# frekvensHack_schematic.net
KiCad netlist of a schematic drawn in EAGLE
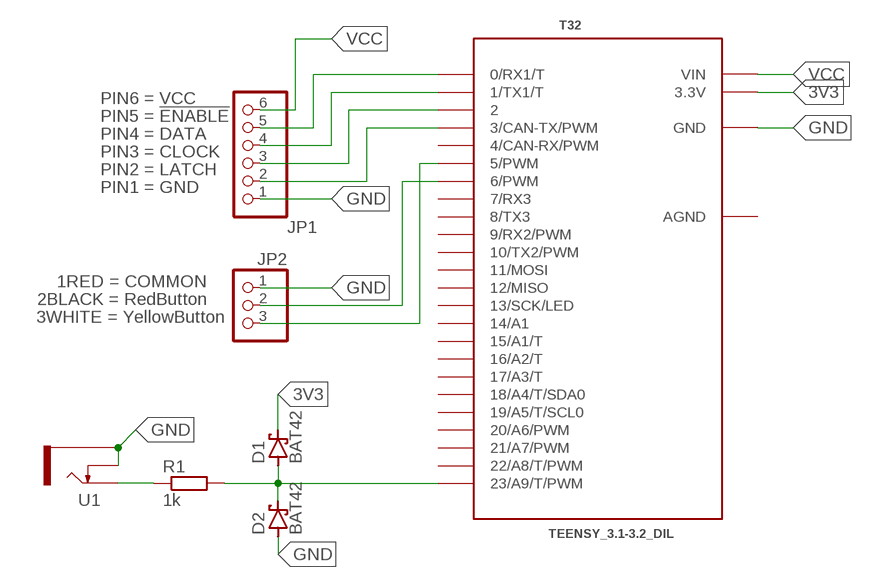
[diagram p0: schematic, sheet 1]

(export (version "E")
  (design (tool "Eeschema 10.0.6"))
  (components
    (comp (ref "D1")
      (value "BAT42")
      (footprint "eagle-import:DO35-10")
      (libsource (lib "eagle-import") (part "BAT42"))
    )
    (comp (ref "D2")
      (value "BAT42")
      (footprint "eagle-import:DO35-10")
      (libsource (lib "eagle-import") (part "BAT42"))
    )
    (comp (ref "JP1")
      (value "PINHD-1X6")
      (footprint "eagle-import:1X06")
      (fields
        (field (name "PIN1") "GND")
        (field (name "PIN2") "LATCH")
        (field (name "PIN3") "CLOCK")
        (field (name "PIN4") "DATA")
        (field (name "PIN5") "!ENABLE")
        (field (name "PIN6") "VCC")
      )
      (libsource (lib "eagle-import") (part "PINHD-1X6"))
    )
    (comp (ref "JP2")
      (value "PINHD-1X3")
      (footprint "eagle-import:1X03")
      (fields
        (field (name "1RED") "COMMON")
        (field (name "2BLACK") "RedButton")
        (field (name "3WHITE") "YellowButton")
      )
      (libsource (lib "eagle-import") (part "PINHD-1X3"))
    )
    (comp (ref "R1")
      (value "1k")
      (footprint "eagle-import:10MM_RESISTOR")
      (libsource (lib "eagle-import") (part "RESISTOR10MM_RESISTOR"))
    )
    (comp (ref "T32")
      (value "TEENSY_3.1-3.2_DIL")
      (footprint "eagle-import:TEENSY_3.0-3.2&LC_DIL")
      (libsource (lib "eagle-import") (part "TEENSY_3.1-3.2_DIL"))
    )
    (comp (ref "U1")
      (value "THONKICONNNEW")
      (footprint "eagle-import:WQP-PJ301M-12_JACK")
      (libsource (lib "eagle-import") (part "THONKICONNNEW"))
    )
  )
  (nets
    (net (code "1") (name "/AGND") (class "Default")
      (node (ref "T32") (pin "AGND") (pinfunction "AGND_AGND") (pintype "power_in"))
    )
    (net (code "2") (name "3V3") (class "Default")
      (node (ref "D1") (pin "C") (pinfunction "C_C") (pintype "passive"))
      (node (ref "T32") (pin "3.3V") (pinfunction "3.3V_3.3V") (pintype "power_in"))
    )
    (net (code "3") (name "GND") (class "Default")
      (node (ref "D2") (pin "A") (pinfunction "A_A") (pintype "passive"))
      (node (ref "JP1") (pin "1") (pinfunction "1_1") (pintype "passive"))
      (node (ref "JP2") (pin "1") (pinfunction "1_1") (pintype "passive"))
      (node (ref "T32") (pin "GND") (pinfunction "GND_GND") (pintype "power_in"))
      (node (ref "U1") (pin "P$2_SWITCH") (pinfunction "SWITCH_P$2_SWITCH") (pintype "passive"))
      (node (ref "U1") (pin "P$3_SLEEVE") (pinfunction "SLEEVE_P$3_SLEEVE") (pintype "passive"))
    )
    (net (code "4") (name "Net-(JP1-Pad3)") (class "Default")
      (node (ref "JP1") (pin "3") (pinfunction "3_3") (pintype "passive"))
      (node (ref "T32") (pin "2") (pinfunction "2_2") (pintype "bidirectional"))
    )
    (net (code "5") (name "Net-(T32-0{slash}RX1{slash}T)") (class "Default")
      (node (ref "JP1") (pin "5") (pinfunction "5_5") (pintype "passive"))
      (node (ref "T32") (pin "0") (pinfunction "0/RX1/T_0") (pintype "bidirectional"))
    )
    (net (code "6") (name "Net-(T32-1{slash}TX1{slash}T)") (class "Default")
      (node (ref "JP1") (pin "4") (pinfunction "4_4") (pintype "passive"))
      (node (ref "T32") (pin "1") (pinfunction "1/TX1/T_1") (pintype "bidirectional"))
    )
    (net (code "7") (name "Net-(T32-3{slash}CAN-TX{slash}PWM)") (class "Default")
      (node (ref "JP1") (pin "2") (pinfunction "2_2") (pintype "passive"))
      (node (ref "T32") (pin "3") (pinfunction "3/CAN-TX/PWM_3") (pintype "bidirectional"))
    )
    (net (code "8") (name "Net-(T32-5{slash}PWM)") (class "Default")
      (node (ref "JP2") (pin "3") (pinfunction "3_3") (pintype "passive"))
      (node (ref "T32") (pin "5") (pinfunction "5/PWM_5") (pintype "bidirectional"))
    )
    (net (code "9") (name "Net-(T32-6{slash}PWM)") (class "Default")
      (node (ref "JP2") (pin "2") (pinfunction "2_2") (pintype "passive"))
      (node (ref "T32") (pin "6") (pinfunction "6/PWM_6") (pintype "bidirectional"))
    )
    (net (code "10") (name "Net-(T32-23{slash}A9{slash}T{slash}PWM)") (class "Default")
      (node (ref "D1") (pin "A") (pinfunction "A_A") (pintype "passive"))
      (node (ref "D2") (pin "C") (pinfunction "C_C") (pintype "passive"))
      (node (ref "R1") (pin "2") (pinfunction "2_2") (pintype "passive"))
      (node (ref "T32") (pin "23/A9") (pinfunction "23/A9/T/PWM_23/A9") (pintype "bidirectional"))
    )
    (net (code "11") (name "Net-(U1-TIP)") (class "Default")
      (node (ref "R1") (pin "1") (pinfunction "1_1") (pintype "passive"))
      (node (ref "U1") (pin "P$1_TIP") (pinfunction "TIP_P$1_TIP") (pintype "passive"))
    )
    (net (code "12") (name "VCC") (class "Default")
      (node (ref "JP1") (pin "6") (pinfunction "6_6") (pintype "passive"))
      (node (ref "T32") (pin "VIN") (pinfunction "VIN_VIN") (pintype "power_in"))
    )
    (net (code "13") (name "unconnected-(T32-4{slash}CAN-RX{slash}PWM-Pad4)") (class "Default")
      (node (ref "T32") (pin "4") (pinfunction "4/CAN-RX/PWM_4") (pintype "bidirectional"))
    )
    (net (code "14") (name "unconnected-(T32-7{slash}RX3-Pad7)") (class "Default")
      (node (ref "T32") (pin "7") (pinfunction "7/RX3_7") (pintype "bidirectional"))
    )
    (net (code "15") (name "unconnected-(T32-8{slash}TX3-Pad8)") (class "Default")
      (node (ref "T32") (pin "8") (pinfunction "8/TX3_8") (pintype "bidirectional"))
    )
    (net (code "16") (name "unconnected-(T32-9{slash}RX2{slash}PWM-Pad9)") (class "Default")
      (node (ref "T32") (pin "9") (pinfunction "9/RX2/PWM_9") (pintype "bidirectional"))
    )
    (net (code "17") (name "unconnected-(T32-10{slash}TX2{slash}PWM-Pad10)") (class "Default")
      (node (ref "T32") (pin "10") (pinfunction "10/TX2/PWM_10") (pintype "bidirectional"))
    )
    (net (code "18") (name "unconnected-(T32-11{slash}MOSI-Pad11)") (class "Default")
      (node (ref "T32") (pin "11") (pinfunction "11/MOSI_11") (pintype "bidirectional"))
    )
    (net (code "19") (name "unconnected-(T32-12{slash}MISO-Pad12)") (class "Default")
      (node (ref "T32") (pin "12") (pinfunction "12/MISO_12") (pintype "bidirectional"))
    )
    (net (code "20") (name "unconnected-(T32-13{slash}SCK{slash}LED-Pad13)") (class "Default")
      (node (ref "T32") (pin "13") (pinfunction "13/SCK/LED_13") (pintype "bidirectional"))
    )
    (net (code "21") (name "unconnected-(T32-14{slash}A1-Pad14{slash}A0)") (class "Default")
      (node (ref "T32") (pin "14/A0") (pinfunction "14/A1_14/A0") (pintype "bidirectional"))
    )
    (net (code "22") (name "unconnected-(T32-15{slash}A1{slash}T-Pad15{slash}A1)") (class "Default")
      (node (ref "T32") (pin "15/A1") (pinfunction "15/A1/T_15/A1") (pintype "bidirectional"))
    )
    (net (code "23") (name "unconnected-(T32-16{slash}A2{slash}T-Pad16{slash}A2)") (class "Default")
      (node (ref "T32") (pin "16/A2") (pinfunction "16/A2/T_16/A2") (pintype "bidirectional"))
    )
    (net (code "24") (name "unconnected-(T32-17{slash}A3{slash}T-Pad17{slash}A3)") (class "Default")
      (node (ref "T32") (pin "17/A3") (pinfunction "17/A3/T_17/A3") (pintype "bidirectional"))
    )
    (net (code "25") (name "unconnected-(T32-18{slash}A4{slash}T{slash}SDA0-Pad18{slash}A4)") (class "Default")
      (node (ref "T32") (pin "18/A4") (pinfunction "18/A4/T/SDA0_18/A4") (pintype "bidirectional"))
    )
    (net (code "26") (name "unconnected-(T32-19{slash}A5{slash}T{slash}SCL0-Pad19{slash}A5)") (class "Default")
      (node (ref "T32") (pin "19/A5") (pinfunction "19/A5/T/SCL0_19/A5") (pintype "bidirectional"))
    )
    (net (code "27") (name "unconnected-(T32-20{slash}A6{slash}PWM-Pad20{slash}A6)") (class "Default")
      (node (ref "T32") (pin "20/A6") (pinfunction "20/A6/PWM_20/A6") (pintype "bidirectional"))
    )
    (net (code "28") (name "unconnected-(T32-21{slash}A7{slash}PWM-Pad21{slash}A7)") (class "Default")
      (node (ref "T32") (pin "21/A7") (pinfunction "21/A7/PWM_21/A7") (pintype "bidirectional"))
    )
    (net (code "29") (name "unconnected-(T32-22{slash}A8{slash}T{slash}PWM-Pad22{slash}A8)") (class "Default")
      (node (ref "T32") (pin "22/A8") (pinfunction "22/A8/T/PWM_22/A8") (pintype "bidirectional"))
    )
  )
)
